# ADC.net
KiCad netlist of a schematic drawn in Altium Designer
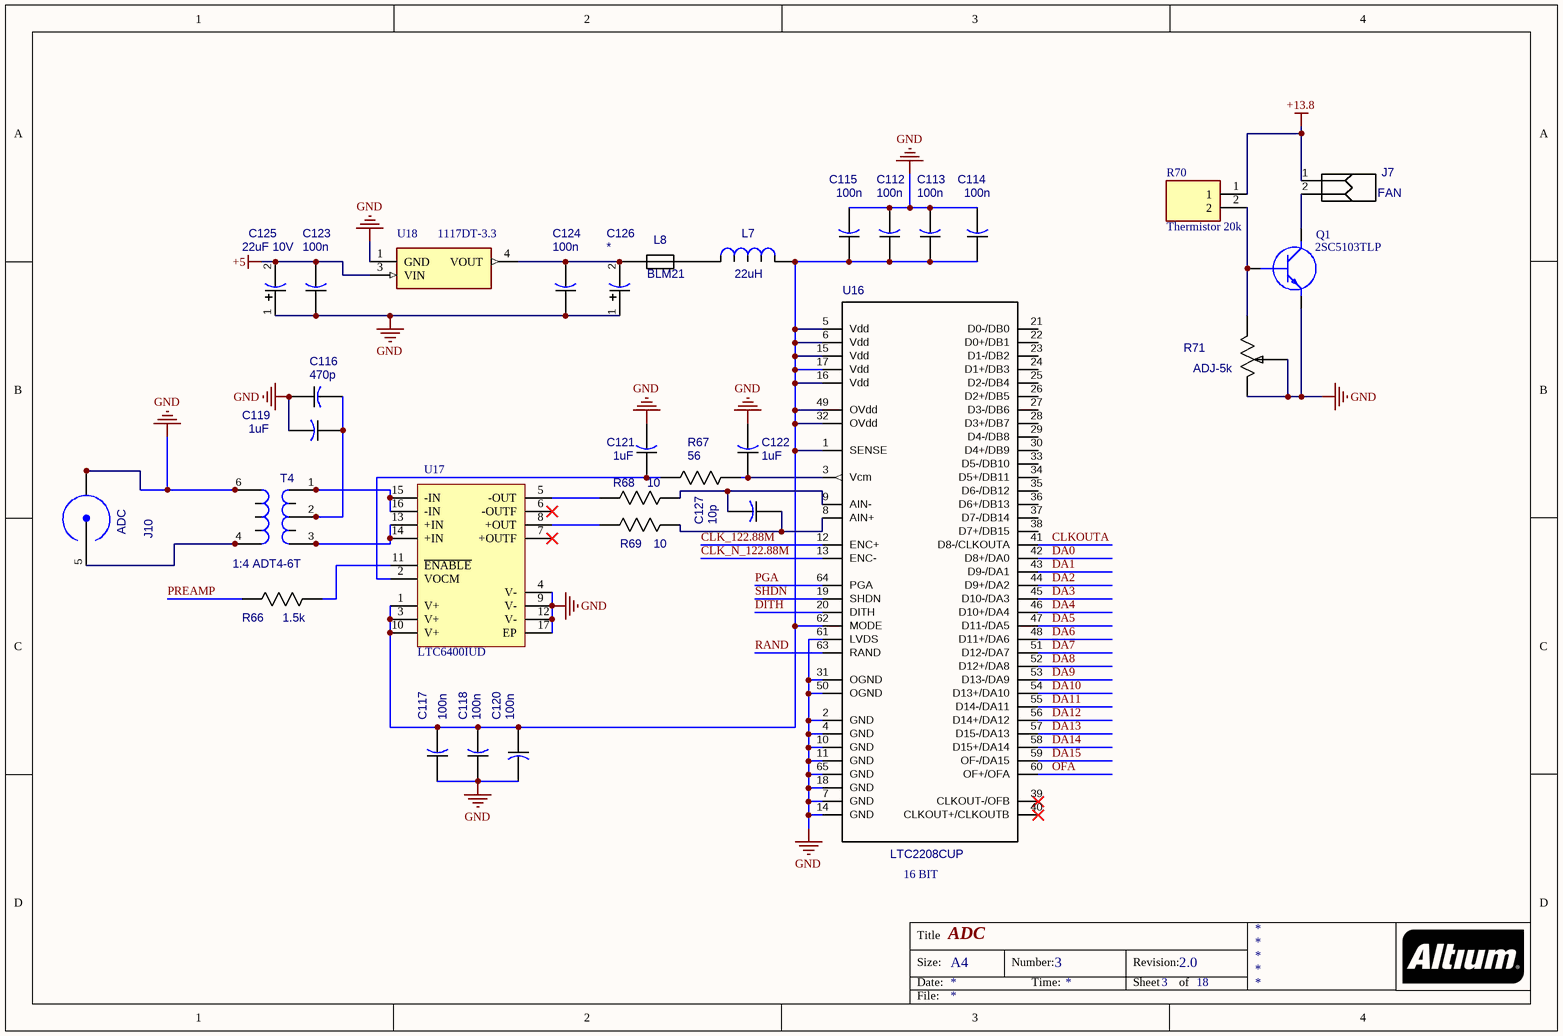
[diagram p0: ADC.SchDoc]

(export (version "E")
  (design (tool "Eeschema 10.0.6"))
  (components
    (comp (ref "C112")
      (value "100n")
      (footprint "CAP_0805")
      (description "CAP_0805")
      (libsource (lib "*") (part "CAP_0805"))
    )
    (comp (ref "C113")
      (value "100n")
      (footprint "CAP_0805")
      (description "CAP_0805")
      (libsource (lib "*") (part "CAP_0805"))
    )
    (comp (ref "C114")
      (value "100n")
      (footprint "CAP_0805")
      (description "CAP_0805")
      (libsource (lib "*") (part "CAP_0805"))
    )
    (comp (ref "C115")
      (value "100n")
      (footprint "CAP_0805")
      (description "CAP_0805")
      (libsource (lib "*") (part "CAP_0805"))
    )
    (comp (ref "C116")
      (value "470p")
      (footprint "CAP_0805")
      (description "CAP_0805")
      (libsource (lib "*") (part "CAP_0805"))
    )
    (comp (ref "C117")
      (value "100n")
      (footprint "CAP_0805")
      (description "CAP_0805")
      (libsource (lib "*") (part "CAP_0805"))
    )
    (comp (ref "C118")
      (value "100n")
      (footprint "CAP_0805")
      (description "CAP_0805")
      (libsource (lib "*") (part "CAP_0805"))
    )
    (comp (ref "C119")
      (value "1uF")
      (footprint "CAP_0805")
      (description "CAP_0805")
      (libsource (lib "*") (part "CAP_0805"))
    )
    (comp (ref "C120")
      (value "100n")
      (footprint "CAP_0805")
      (description "CAP_0805")
      (libsource (lib "*") (part "CAP_0805"))
    )
    (comp (ref "C121")
      (value "1uF")
      (footprint "CAP_0805")
      (description "CAP_0805")
      (libsource (lib "*") (part "CAP_0805"))
    )
    (comp (ref "C122")
      (value "1uF")
      (footprint "CAP_0805")
      (description "CAP_0805")
      (libsource (lib "*") (part "CAP_0805"))
    )
    (comp (ref "C123")
      (value "100n")
      (footprint "CAP_0805")
      (description "CAP_0805")
      (libsource (lib "*") (part "CAP_0805"))
    )
    (comp (ref "C124")
      (value "100n")
      (footprint "CAP_0805")
      (description "CAP_0805")
      (libsource (lib "*") (part "CAP_0805"))
    )
    (comp (ref "C125")
      (value "22uF 10V")
      (footprint "CAPAE_4.3x4.3h5.4")
      (description "CAPAE_4.3x4.3h5.4")
      (libsource (lib "MOTHERBOARD") (part "CAPAE_4.3x4.3h5.4"))
    )
    (comp (ref "C126")
      (value "22uF 10V")
      (footprint "CAPAE_4.3x4.3h5.4")
      (description "CAPAE_4.3x4.3h5.4")
      (fields (field (name "ALTIUM_VALUE") "*"))
      (libsource (lib "MOTHERBOARD") (part "CAPAE_4.3x4.3h5.4"))
    )
    (comp (ref "C127")
      (value "10p")
      (footprint "CAP_0805")
      (description "CAP_0805")
      (libsource (lib "*") (part "CAP_0805"))
    )
    (comp (ref "J7")
      (value "FAN")
      (footprint "51022-0200")
      (description "51022-0200")
      (libsource (lib "*") (part "51022-0200"))
    )
    (comp (ref "J10")
      (value "ADC")
      (footprint "31-5431")
      (description "SMA")
      (libsource (lib "RF-UNIT_1") (part "31-5431"))
    )
    (comp (ref "L7")
      (value "22uH")
      (footprint "CAPAE_6.6x6.6h5.4")
      (description "IND_1206")
      (libsource (lib "*") (part "IND_1206"))
    )
    (comp (ref "L8")
      (value "BLM21")
      (footprint "CAP_0805")
      (libsource (lib "MOTHERBOARD_1") (part "IND_FERRITE_BEAD"))
    )
    (comp (ref "Q1")
      (value "2SC5103TLP")
      (footprint "SamacSys:2SC5103TLQ")
      (description "Transistor BJT NPN")
      (fields (field (name "MOUSER PART NUMBER") "755-2SC5103TLP"))
      (libsource (lib "*") (part "2SC5103TLP"))
    )
    (comp (ref "R66")
      (value "1.5k")
      (footprint "RES_0805")
      (description "RES_0805")
      (libsource (lib "") (part "RES_0805_1"))
    )
    (comp (ref "R67")
      (value "56")
      (footprint "RES_0805")
      (description "RES_0805")
      (libsource (lib "*") (part "RES_0805"))
    )
    (comp (ref "R68")
      (value "10")
      (footprint "RES_0603")
      (description "RES_0603")
      (libsource (lib "*") (part "RES_0603"))
    )
    (comp (ref "R69")
      (value "10")
      (footprint "RES_0603")
      (description "RES_0603")
      (libsource (lib "*") (part "RES_0603"))
    )
    (comp (ref "R70")
      (value "Thermistor 20k")
      (footprint "MF52A103F3950A1")
      (description "Thermistor")
      (fields (field (name "MANUFACTURER_PART_NUMBER") "MF52A103F3950(A1)"))
      (libsource (lib "*") (part "MF52A103F3950_A1_"))
    )
    (comp (ref "R71")
      (value "ADJ-5k")
      (footprint "306J")
      (description "306J")
      (libsource (lib "*") (part "306J"))
    )
    (comp (ref "T4")
      (value "1:4 ADT4-6T")
      (footprint "TRANSF_ACORE2")
      (description "Transformer")
      (libsource (lib "MOTHERBOARD_1") (part "TRANSF_ACORE2"))
    )
    (comp (ref "U16") (value "LTC2208CUP") (footprint "LTC2208CUP") (libsource (lib "*") (part "LTC2208CUP")))
    (comp (ref "U17")
      (value "LTC6400IUD")
      (footprint "LT-UD-16_N")
      (fields
        (field (name "MANUFACTURER") "Linear Technology")
        (field (name "LINEAR TECHNOLOGY PART NUMBER") "LTC6400-20")
        (field (name "PARTNUMBER") "LTC6400IUD-20#PBF")
      )
      (libsource (lib "Altium Content Vault") (part "LT-LTC640X-X-16"))
    )
    (comp (ref "U18")
      (value "1117DT-3.3")
      (footprint "SamacSys:TO228P991X238-3N")
      (description "LD1117DT33 DPAK")
      (fields
        (field (name "MANUFACTURER_PART_NUMBER") "LM1117DT-ADJ")
        (field (name "MOUSER PART NUMBER") "926-LM1117DT-ADJ")
      )
      (libsource (lib "*") (part "LM1117DT-ADJ"))
    )
  )
  (nets
    (net (code "1") (name "+5") (class "Default")
      (node (ref "C123") (pin "2") (pinfunction "2_2") (pintype "passive"))
      (node (ref "C125") (pin "2") (pinfunction "MINUS_2") (pintype "passive"))
      (node (ref "U18") (pin "3") (pinfunction "VIN_3") (pintype "input"))
    )
    (net (code "2") (name "+13.8") (class "Default")
      (node (ref "J7") (pin "1") (pinfunction "1_1") (pintype "passive"))
      (node (ref "R70") (pin "1") (pinfunction "1_1") (pintype "passive"))
    )
    (net (code "3") (name "/CLKOUTA") (class "Default")
      (node (ref "U16") (pin "41") (pinfunction "D8-/CLKOUTA_41") (pintype "passive"))
    )
    (net (code "4") (name "/CLK_122.88M") (class "Default")
      (node (ref "U16") (pin "12") (pinfunction "ENC+_12") (pintype "passive"))
    )
    (net (code "5") (name "/CLK_N_122.88M") (class "Default")
      (node (ref "U16") (pin "13") (pinfunction "ENC-_13") (pintype "passive"))
    )
    (net (code "6") (name "/DA0") (class "Default")
      (node (ref "U16") (pin "42") (pinfunction "D8+/DA0_42") (pintype "passive"))
    )
    (net (code "7") (name "/DA1") (class "Default")
      (node (ref "U16") (pin "43") (pinfunction "D9-/DA1_43") (pintype "passive"))
    )
    (net (code "8") (name "/DA2") (class "Default")
      (node (ref "U16") (pin "44") (pinfunction "D9+/DA2_44") (pintype "passive"))
    )
    (net (code "9") (name "/DA3") (class "Default")
      (node (ref "U16") (pin "45") (pinfunction "D10-/DA3_45") (pintype "passive"))
    )
    (net (code "10") (name "/DA4") (class "Default")
      (node (ref "U16") (pin "46") (pinfunction "D10+/DA4_46") (pintype "passive"))
    )
    (net (code "11") (name "/DA5") (class "Default")
      (node (ref "U16") (pin "47") (pinfunction "D11-/DA5_47") (pintype "passive"))
    )
    (net (code "12") (name "/DA6") (class "Default")
      (node (ref "U16") (pin "48") (pinfunction "D11+/DA6_48") (pintype "passive"))
    )
    (net (code "13") (name "/DA7") (class "Default")
      (node (ref "U16") (pin "51") (pinfunction "D12-/DA7_51") (pintype "passive"))
    )
    (net (code "14") (name "/DA8") (class "Default")
      (node (ref "U16") (pin "52") (pinfunction "D12+/DA8_52") (pintype "passive"))
    )
    (net (code "15") (name "/DA9") (class "Default")
      (node (ref "U16") (pin "53") (pinfunction "D13-/DA9_53") (pintype "passive"))
    )
    (net (code "16") (name "/DA10") (class "Default")
      (node (ref "U16") (pin "54") (pinfunction "D13+/DA10_54") (pintype "passive"))
    )
    (net (code "17") (name "/DA11") (class "Default")
      (node (ref "U16") (pin "55") (pinfunction "D14-/DA11_55") (pintype "passive"))
    )
    (net (code "18") (name "/DA12") (class "Default")
      (node (ref "U16") (pin "56") (pinfunction "D14+/DA12_56") (pintype "passive"))
    )
    (net (code "19") (name "/DA13") (class "Default")
      (node (ref "U16") (pin "57") (pinfunction "D15-/DA13_57") (pintype "passive"))
    )
    (net (code "20") (name "/DA14") (class "Default")
      (node (ref "U16") (pin "58") (pinfunction "D15+/DA14_58") (pintype "passive"))
    )
    (net (code "21") (name "/DA15") (class "Default")
      (node (ref "U16") (pin "59") (pinfunction "OF-/DA15_59") (pintype "passive"))
    )
    (net (code "22") (name "/DITH") (class "Default")
      (node (ref "U16") (pin "20") (pinfunction "DITH_20") (pintype "passive"))
    )
    (net (code "23") (name "/OFA") (class "Default")
      (node (ref "U16") (pin "60") (pinfunction "OF+/OFA_60") (pintype "passive"))
    )
    (net (code "24") (name "/PGA") (class "Default")
      (node (ref "U16") (pin "64") (pinfunction "PGA_64") (pintype "passive"))
    )
    (net (code "25") (name "/PREAMP") (class "Default")
      (node (ref "R66") (pin "2") (pinfunction "1_2") (pintype "passive"))
    )
    (net (code "26") (name "/RAND") (class "Default")
      (node (ref "U16") (pin "63") (pinfunction "RAND_63") (pintype "passive"))
    )
    (net (code "27") (name "/SHDN") (class "Default")
      (node (ref "U16") (pin "19") (pinfunction "SHDN_19") (pintype "passive"))
    )
    (net (code "28") (name "GND") (class "Default")
      (node (ref "C112") (pin "2") (pinfunction "2_2") (pintype "passive"))
      (node (ref "C113") (pin "2") (pinfunction "2_2") (pintype "passive"))
      (node (ref "C114") (pin "2") (pinfunction "2_2") (pintype "passive"))
      (node (ref "C115") (pin "2") (pinfunction "2_2") (pintype "passive"))
      (node (ref "C116") (pin "1") (pinfunction "1_1") (pintype "passive"))
      (node (ref "C117") (pin "1") (pinfunction "1_1") (pintype "passive"))
      (node (ref "C118") (pin "1") (pinfunction "1_1") (pintype "passive"))
      (node (ref "C119") (pin "2") (pinfunction "2_2") (pintype "passive"))
      (node (ref "C120") (pin "2") (pinfunction "2_2") (pintype "passive"))
      (node (ref "C121") (pin "2") (pinfunction "2_2") (pintype "passive"))
      (node (ref "C122") (pin "2") (pinfunction "2_2") (pintype "passive"))
      (node (ref "C123") (pin "1") (pinfunction "1_1") (pintype "passive"))
      (node (ref "C124") (pin "1") (pinfunction "1_1") (pintype "passive"))
      (node (ref "C125") (pin "1") (pinfunction "PLUS_1") (pintype "passive"))
      (node (ref "C126") (pin "1") (pinfunction "PLUS_1") (pintype "passive"))
      (node (ref "J10") (pin "1") (pinfunction "GND_1") (pintype "passive"))
      (node (ref "J10") (pin "2") (pinfunction "GND_2") (pintype "passive"))
      (node (ref "J10") (pin "3") (pinfunction "GND_3") (pintype "passive"))
      (node (ref "J10") (pin "4") (pinfunction "GND_4") (pintype "passive"))
      (node (ref "Q1") (pin "3") (pinfunction "E_3") (pintype "passive"))
      (node (ref "R71") (pin "1") (pinfunction "CCW_1") (pintype "passive"))
      (node (ref "R71") (pin "2") (pinfunction "W_2") (pintype "passive"))
      (node (ref "T4") (pin "10") (pinfunction "0_10") (pintype "passive"))
      (node (ref "T4") (pin "6") (pinfunction "P2_6") (pintype "passive"))
      (node (ref "U16") (pin "10") (pinfunction "GND_10") (pintype "passive"))
      (node (ref "U16") (pin "11") (pinfunction "GND_11") (pintype "passive"))
      (node (ref "U16") (pin "14") (pinfunction "GND_14") (pintype "passive"))
      (node (ref "U16") (pin "18") (pinfunction "GND_18") (pintype "passive"))
      (node (ref "U16") (pin "2") (pinfunction "GND_2") (pintype "passive"))
      (node (ref "U16") (pin "31") (pinfunction "OGND_31") (pintype "passive"))
      (node (ref "U16") (pin "4") (pinfunction "GND_4") (pintype "passive"))
      (node (ref "U16") (pin "50") (pinfunction "OGND_50") (pintype "passive"))
      (node (ref "U16") (pin "61") (pinfunction "LVDS_61") (pintype "passive"))
      (node (ref "U16") (pin "65") (pinfunction "GND_65") (pintype "passive"))
      (node (ref "U16") (pin "7") (pinfunction "GND_7") (pintype "passive"))
      (node (ref "U17") (pin "12") (pinfunction "V-_12") (pintype "power_in"))
      (node (ref "U17") (pin "17") (pinfunction "EP_17") (pintype "power_in"))
      (node (ref "U17") (pin "4") (pinfunction "V-_4") (pintype "power_in"))
      (node (ref "U17") (pin "9") (pinfunction "V-_9") (pintype "power_in"))
      (node (ref "U18") (pin "1") (pinfunction "GND_1") (pintype "passive"))
    )
    (net (code "29") (name "Net-(C126-MINUS)") (class "Default")
      (node (ref "C124") (pin "2") (pinfunction "2_2") (pintype "passive"))
      (node (ref "C126") (pin "2") (pinfunction "MINUS_2") (pintype "passive"))
      (node (ref "L8") (pin "1") (pinfunction "1_1") (pintype "passive"))
      (node (ref "U18") (pin "4") (pinfunction "VOUT_4") (pintype "output"))
    )
    (net (code "30") (name "Net-(J10-CON)") (class "Default")
      (node (ref "J10") (pin "5") (pinfunction "CON_5") (pintype "passive"))
      (node (ref "T4") (pin "11") (pinfunction "0_11") (pintype "passive"))
      (node (ref "T4") (pin "4") (pinfunction "P1_4") (pintype "passive"))
    )
    (net (code "31") (name "Net-(L7-Pad1)") (class "Default")
      (node (ref "L7") (pin "1") (pinfunction "1_1") (pintype "passive"))
      (node (ref "L8") (pin "2") (pinfunction "2_2") (pintype "passive"))
    )
    (net (code "32") (name "Net-(Q1-B)") (class "Default")
      (node (ref "Q1") (pin "1") (pinfunction "B_1") (pintype "passive"))
      (node (ref "R70") (pin "2") (pinfunction "2_2") (pintype "passive"))
      (node (ref "R71") (pin "3") (pinfunction "CW_3") (pintype "passive"))
    )
    (net (code "33") (name "Net-(Q1-C)") (class "Default")
      (node (ref "J7") (pin "2") (pinfunction "2_2") (pintype "passive"))
      (node (ref "Q1") (pin "2") (pinfunction "C_2") (pintype "passive"))
    )
    (net (code "34") (name "Net-(R66-2)") (class "Default")
      (node (ref "R66") (pin "1") (pinfunction "2_1") (pintype "passive"))
      (node (ref "U17") (pin "11") (pinfunction "~{ENABLE}_11") (pintype "passive"))
    )
    (net (code "35") (name "Net-(T4-S1)") (class "Default")
      (node (ref "T4") (pin "3") (pinfunction "S1_3") (pintype "passive"))
      (node (ref "T4") (pin "9") (pinfunction "0_9") (pintype "passive"))
      (node (ref "U17") (pin "13") (pinfunction "+IN_13") (pintype "passive"))
      (node (ref "U17") (pin "14") (pinfunction "+IN_14") (pintype "passive"))
    )
    (net (code "36") (name "Net-(T4-S2)") (class "Default")
      (node (ref "C116") (pin "2") (pinfunction "2_2") (pintype "passive"))
      (node (ref "C119") (pin "1") (pinfunction "1_1") (pintype "passive"))
      (node (ref "T4") (pin "2") (pinfunction "S2_2") (pintype "passive"))
      (node (ref "T4") (pin "8") (pinfunction "0_8") (pintype "passive"))
    )
    (net (code "37") (name "Net-(T4-S3)") (class "Default")
      (node (ref "T4") (pin "1") (pinfunction "S3_1") (pintype "passive"))
      (node (ref "T4") (pin "7") (pinfunction "0_7") (pintype "passive"))
      (node (ref "U17") (pin "15") (pinfunction "-IN_15") (pintype "passive"))
      (node (ref "U17") (pin "16") (pinfunction "-IN_16") (pintype "passive"))
    )
    (net (code "38") (name "Net-(U16-AIN+)") (class "Default")
      (node (ref "C127") (pin "1") (pinfunction "1_1") (pintype "passive"))
      (node (ref "R69") (pin "2") (pinfunction "2_2") (pintype "passive"))
      (node (ref "U16") (pin "8") (pinfunction "AIN+_8") (pintype "passive"))
    )
    (net (code "39") (name "Net-(U16-AIN-)") (class "Default")
      (node (ref "C127") (pin "2") (pinfunction "2_2") (pintype "passive"))
      (node (ref "R68") (pin "2") (pinfunction "2_2") (pintype "passive"))
      (node (ref "U16") (pin "9") (pinfunction "AIN-_9") (pintype "passive"))
    )
    (net (code "40") (name "Net-(U16-MODE)") (class "Default")
      (node (ref "C112") (pin "1") (pinfunction "1_1") (pintype "passive"))
      (node (ref "C113") (pin "1") (pinfunction "1_1") (pintype "passive"))
      (node (ref "C114") (pin "1") (pinfunction "1_1") (pintype "passive"))
      (node (ref "C115") (pin "1") (pinfunction "1_1") (pintype "passive"))
      (node (ref "C117") (pin "2") (pinfunction "2_2") (pintype "passive"))
      (node (ref "C118") (pin "2") (pinfunction "2_2") (pintype "passive"))
      (node (ref "C120") (pin "1") (pinfunction "1_1") (pintype "passive"))
      (node (ref "L7") (pin "2") (pinfunction "2_2") (pintype "passive"))
      (node (ref "U16") (pin "1") (pinfunction "SENSE_1") (pintype "passive"))
      (node (ref "U16") (pin "15") (pinfunction "Vdd_15") (pintype "passive"))
      (node (ref "U16") (pin "16") (pinfunction "Vdd_16") (pintype "passive"))
      (node (ref "U16") (pin "17") (pinfunction "Vdd_17") (pintype "passive"))
      (node (ref "U16") (pin "32") (pinfunction "OVdd_32") (pintype "passive"))
      (node (ref "U16") (pin "49") (pinfunction "OVdd_49") (pintype "passive"))
      (node (ref "U16") (pin "5") (pinfunction "Vdd_5") (pintype "passive"))
      (node (ref "U16") (pin "6") (pinfunction "Vdd_6") (pintype "passive"))
      (node (ref "U16") (pin "62") (pinfunction "MODE_62") (pintype "passive"))
      (node (ref "U17") (pin "1") (pinfunction "V+_1") (pintype "power_in"))
      (node (ref "U17") (pin "10") (pinfunction "V+_10") (pintype "power_in"))
      (node (ref "U17") (pin "3") (pinfunction "V+_3") (pintype "power_in"))
    )
    (net (code "41") (name "Net-(U16-Vcm)") (class "Default")
      (node (ref "C122") (pin "1") (pinfunction "1_1") (pintype "passive"))
      (node (ref "R67") (pin "2") (pinfunction "2_2") (pintype "passive"))
      (node (ref "U16") (pin "3") (pinfunction "Vcm_3") (pintype "output"))
    )
    (net (code "42") (name "Net-(U17-+OUT)") (class "Default")
      (node (ref "R69") (pin "1") (pinfunction "1_1") (pintype "passive"))
      (node (ref "U17") (pin "8") (pinfunction "+OUT_8") (pintype "passive"))
    )
    (net (code "43") (name "Net-(U17--OUT)") (class "Default")
      (node (ref "R68") (pin "1") (pinfunction "1_1") (pintype "passive"))
      (node (ref "U17") (pin "5") (pinfunction "-OUT_5") (pintype "passive"))
    )
    (net (code "44") (name "Net-(U17-VOCM)") (class "Default")
      (node (ref "C121") (pin "1") (pinfunction "1_1") (pintype "passive"))
      (node (ref "R67") (pin "1") (pinfunction "1_1") (pintype "passive"))
      (node (ref "U17") (pin "2") (pinfunction "VOCM_2") (pintype "passive"))
    )
    (net (code "45") (name "unconnected-(U16-CLKOUT+{slash}CLKOUTB-Pad40)") (class "Default")
      (node (ref "U16") (pin "40") (pinfunction "CLKOUT+/CLKOUTB_40") (pintype "passive+no_connect"))
    )
    (net (code "46") (name "unconnected-(U16-CLKOUT-{slash}OFB-Pad39)") (class "Default")
      (node (ref "U16") (pin "39") (pinfunction "CLKOUT-/OFB_39") (pintype "passive+no_connect"))
    )
    (net (code "47") (name "unconnected-(U16-D0+{slash}DB1-Pad22)") (class "Default")
      (node (ref "U16") (pin "22") (pinfunction "D0+/DB1_22") (pintype "passive"))
    )
    (net (code "48") (name "unconnected-(U16-D0-{slash}DB0-Pad21)") (class "Default")
      (node (ref "U16") (pin "21") (pinfunction "D0-/DB0_21") (pintype "passive"))
    )
    (net (code "49") (name "unconnected-(U16-D1+{slash}DB3-Pad24)") (class "Default")
      (node (ref "U16") (pin "24") (pinfunction "D1+/DB3_24") (pintype "passive"))
    )
    (net (code "50") (name "unconnected-(U16-D1-{slash}DB2-Pad23)") (class "Default")
      (node (ref "U16") (pin "23") (pinfunction "D1-/DB2_23") (pintype "passive"))
    )
    (net (code "51") (name "unconnected-(U16-D2+{slash}DB5-Pad26)") (class "Default")
      (node (ref "U16") (pin "26") (pinfunction "D2+/DB5_26") (pintype "passive"))
    )
    (net (code "52") (name "unconnected-(U16-D2-{slash}DB4-Pad25)") (class "Default")
      (node (ref "U16") (pin "25") (pinfunction "D2-/DB4_25") (pintype "passive"))
    )
    (net (code "53") (name "unconnected-(U16-D3+{slash}DB7-Pad28)") (class "Default")
      (node (ref "U16") (pin "28") (pinfunction "D3+/DB7_28") (pintype "passive"))
    )
    (net (code "54") (name "unconnected-(U16-D3-{slash}DB6-Pad27)") (class "Default")
      (node (ref "U16") (pin "27") (pinfunction "D3-/DB6_27") (pintype "passive"))
    )
    (net (code "55") (name "unconnected-(U16-D4+{slash}DB9-Pad30)") (class "Default")
      (node (ref "U16") (pin "30") (pinfunction "D4+/DB9_30") (pintype "passive"))
    )
    (net (code "56") (name "unconnected-(U16-D4-{slash}DB8-Pad29)") (class "Default")
      (node (ref "U16") (pin "29") (pinfunction "D4-/DB8_29") (pintype "passive"))
    )
    (net (code "57") (name "unconnected-(U16-D5+{slash}DB11-Pad34)") (class "Default")
      (node (ref "U16") (pin "34") (pinfunction "D5+/DB11_34") (pintype "passive"))
    )
    (net (code "58") (name "unconnected-(U16-D5-{slash}DB10-Pad33)") (class "Default")
      (node (ref "U16") (pin "33") (pinfunction "D5-/DB10_33") (pintype "passive"))
    )
    (net (code "59") (name "unconnected-(U16-D6+{slash}DB13-Pad36)") (class "Default")
      (node (ref "U16") (pin "36") (pinfunction "D6+/DB13_36") (pintype "passive"))
    )
    (net (code "60") (name "unconnected-(U16-D6-{slash}DB12-Pad35)") (class "Default")
      (node (ref "U16") (pin "35") (pinfunction "D6-/DB12_35") (pintype "passive"))
    )
    (net (code "61") (name "unconnected-(U16-D7+{slash}DB15-Pad38)") (class "Default")
      (node (ref "U16") (pin "38") (pinfunction "D7+/DB15_38") (pintype "passive"))
    )
    (net (code "62") (name "unconnected-(U16-D7-{slash}DB14-Pad37)") (class "Default")
      (node (ref "U16") (pin "37") (pinfunction "D7-/DB14_37") (pintype "passive"))
    )
    (net (code "63") (name "unconnected-(U17-+OUTF-Pad7)") (class "Default")
      (node (ref "U17") (pin "7") (pinfunction "+OUTF_7") (pintype "passive+no_connect"))
    )
    (net (code "64") (name "unconnected-(U17--OUTF-Pad6)") (class "Default")
      (node (ref "U17") (pin "6") (pinfunction "-OUTF_6") (pintype "passive+no_connect"))
    )
  )
)
